# 10_eMMC.net
KiCad netlist of a schematic drawn in Altium Designer
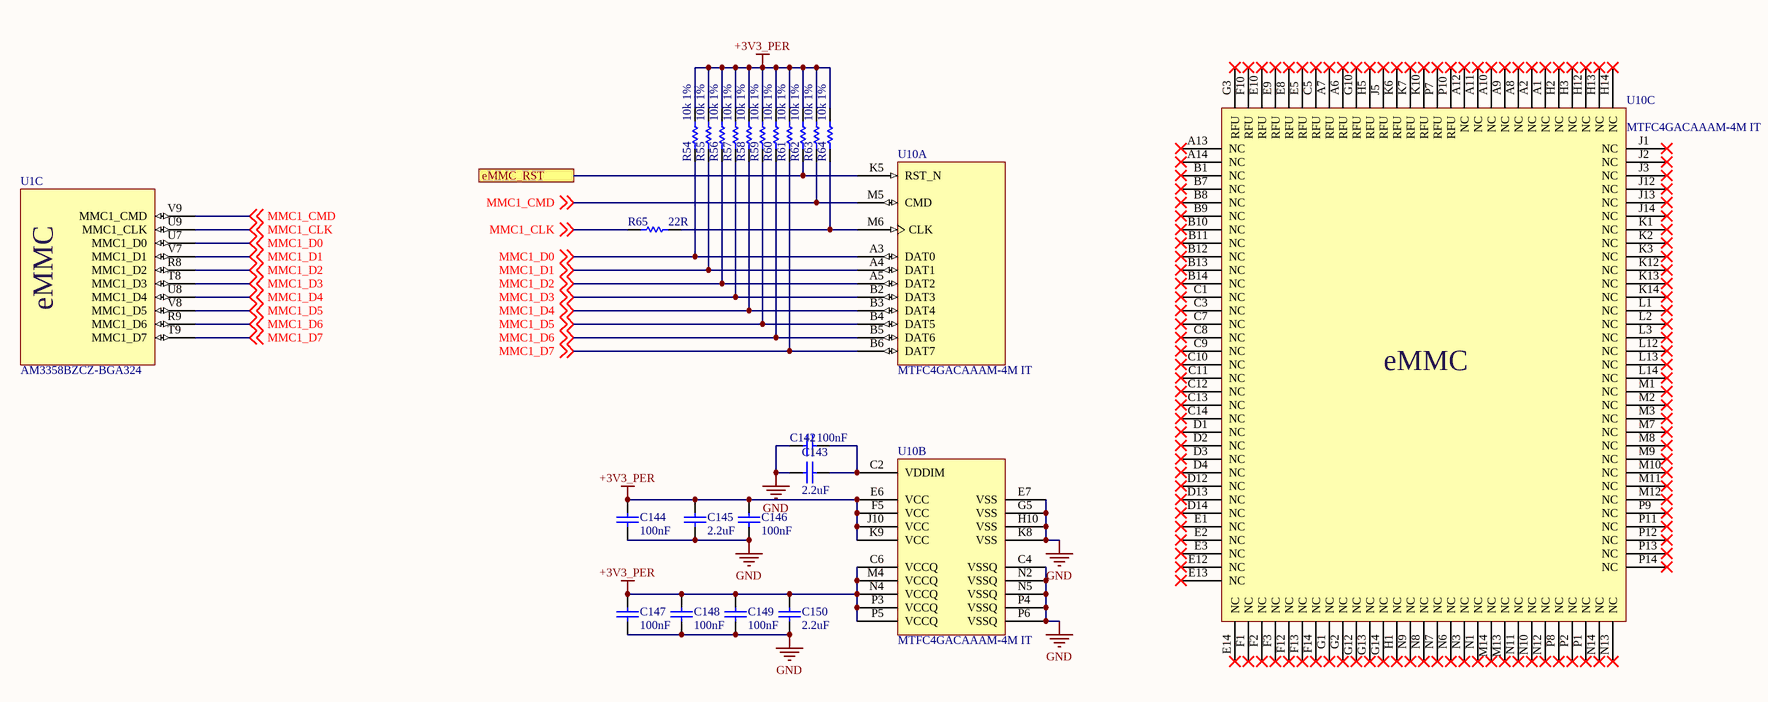
[diagram p0: 10. eMMC.SchDoc]

(export (version "E")
  (design (tool "Eeschema 10.0.6"))
  (components
    (comp (ref "C142")
      (value "100nF")
      (footprint "CAPC1005X60X30LL05T10")
      (description "Chip Capacitor, 0.1 uF, +/- 10%, 16 V, -55 to 125 degC, 0402 (1005 Metric), RoHS, Tape and Reel")
      (fields (field (name "VOLTAGE") "16V") (field (name "TOLERANCE") "10%"))
      (libsource (lib "AM3358_DEV_BOARD") (part "CAP-NP-2"))
    )
    (comp (ref "C143")
      (value "2.2uF")
      (footprint "CAPC1608X90X35ML10T15")
      (description "CAP 2.2uF 10V ±10% 0603 (1608 Metric) Thickness 0.6mm SMD")
      (fields (field (name "MANUFACTURER") "Murata") (field (name "PART NUMBER") "GRM188R71A225KE15D"))
      (libsource (lib "Altium Content Vault") (part "CAP"))
    )
    (comp (ref "C144")
      (value "100nF")
      (footprint "CAPC1005X60X30LL05T10")
      (description "Chip Capacitor, 0.1 uF, +/- 10%, 16 V, -55 to 125 degC, 0402 (1005 Metric), RoHS, Tape and Reel")
      (fields (field (name "VOLTAGE") "16V") (field (name "TOLERANCE") "10%"))
      (libsource (lib "AM3358_DEV_BOARD") (part "CAP-NP-2"))
    )
    (comp (ref "C145")
      (value "2.2uF")
      (footprint "CAPC1005X60X30LL05T10")
      (description "CAP 2.2uF 10V ±10% 0603 (1608 Metric) Thickness 0.6mm SMD")
      (fields (field (name "MANUFACTURER") "Murata") (field (name "PART NUMBER") "GRM188R71A225KE15D"))
      (libsource (lib "AM3358_DEV_BOARD") (part "CAP"))
    )
    (comp (ref "C146")
      (value "100nF")
      (footprint "CAPC1005X60X30LL05T10")
      (description "Chip Capacitor, 0.1 uF, +/- 10%, 16 V, -55 to 125 degC, 0402 (1005 Metric), RoHS, Tape and Reel")
      (fields (field (name "VOLTAGE") "16V") (field (name "TOLERANCE") "10%"))
      (libsource (lib "AM3358_DEV_BOARD") (part "CAP-NP-2"))
    )
    (comp (ref "C147")
      (value "100nF")
      (footprint "CAPC1005X60X30LL05T10")
      (description "Chip Capacitor, 0.1 uF, +/- 10%, 16 V, -55 to 125 degC, 0402 (1005 Metric), RoHS, Tape and Reel")
      (fields (field (name "VOLTAGE") "16V") (field (name "TOLERANCE") "10%"))
      (libsource (lib "AM3358_DEV_BOARD") (part "CAP-NP-2"))
    )
    (comp (ref "C148")
      (value "100nF")
      (footprint "CAPC1005X60X30LL05T10")
      (description "Chip Capacitor, 0.1 uF, +/- 10%, 16 V, -55 to 125 degC, 0402 (1005 Metric), RoHS, Tape and Reel")
      (fields (field (name "VOLTAGE") "16V") (field (name "TOLERANCE") "10%"))
      (libsource (lib "AM3358_DEV_BOARD") (part "CAP-NP-2"))
    )
    (comp (ref "C149")
      (value "100nF")
      (footprint "CAPC1005X60X30LL05T10")
      (description "Chip Capacitor, 0.1 uF, +/- 10%, 16 V, -55 to 125 degC, 0402 (1005 Metric), RoHS, Tape and Reel")
      (fields (field (name "VOLTAGE") "16V") (field (name "TOLERANCE") "10%"))
      (libsource (lib "AM3358_DEV_BOARD") (part "CAP-NP-2"))
    )
    (comp (ref "C150")
      (value "2.2uF")
      (footprint "CAPC1608X90X35ML10T15")
      (description "CAP 2.2uF 10V ±10% 0603 (1608 Metric) Thickness 0.6mm SMD")
      (fields (field (name "MANUFACTURER") "Murata") (field (name "PART NUMBER") "GRM188R71A225KE15D"))
      (libsource (lib "Altium Content Vault") (part "CAP"))
    )
    (comp (ref "R54")
      (value "10k 1%")
      (footprint "RESC1005X40X25LL05T05")
      (description "10k 0.063W 1% 0402 (1005 Metric)  SMD")
      (fields (field (name "MANUFACTURER") "Vishay Dale") (field (name "PART NUMBER") "CRCW040210K0FKED"))
      (libsource (lib "AM3358_DEV_BOARD") (part "RES"))
    )
    (comp (ref "R55")
      (value "10k 1%")
      (footprint "RESC1005X40X25LL05T05")
      (description "10k 0.063W 1% 0402 (1005 Metric)  SMD")
      (fields (field (name "MANUFACTURER") "Vishay Dale") (field (name "PART NUMBER") "CRCW040210K0FKED"))
      (libsource (lib "AM3358_DEV_BOARD") (part "RES"))
    )
    (comp (ref "R56")
      (value "10k 1%")
      (footprint "RESC1005X40X25LL05T05")
      (description "10k 0.063W 1% 0402 (1005 Metric)  SMD")
      (fields (field (name "MANUFACTURER") "Vishay Dale") (field (name "PART NUMBER") "CRCW040210K0FKED"))
      (libsource (lib "AM3358_DEV_BOARD") (part "RES"))
    )
    (comp (ref "R57")
      (value "10k 1%")
      (footprint "RESC1005X40X25LL05T05")
      (description "10k 0.063W 1% 0402 (1005 Metric)  SMD")
      (fields (field (name "MANUFACTURER") "Vishay Dale") (field (name "PART NUMBER") "CRCW040210K0FKED"))
      (libsource (lib "AM3358_DEV_BOARD") (part "RES"))
    )
    (comp (ref "R58")
      (value "10k 1%")
      (footprint "RESC1005X40X25LL05T05")
      (description "10k 0.063W 1% 0402 (1005 Metric)  SMD")
      (fields (field (name "MANUFACTURER") "Vishay Dale") (field (name "PART NUMBER") "CRCW040210K0FKED"))
      (libsource (lib "AM3358_DEV_BOARD") (part "RES"))
    )
    (comp (ref "R59")
      (value "10k 1%")
      (footprint "RESC1005X40X25LL05T05")
      (description "10k 0.063W 1% 0402 (1005 Metric)  SMD")
      (fields (field (name "MANUFACTURER") "Vishay Dale") (field (name "PART NUMBER") "CRCW040210K0FKED"))
      (libsource (lib "AM3358_DEV_BOARD") (part "RES"))
    )
    (comp (ref "R60")
      (value "10k 1%")
      (footprint "RESC1005X40X25LL05T05")
      (description "10k 0.063W 1% 0402 (1005 Metric)  SMD")
      (fields (field (name "MANUFACTURER") "Vishay Dale") (field (name "PART NUMBER") "CRCW040210K0FKED"))
      (libsource (lib "AM3358_DEV_BOARD") (part "RES"))
    )
    (comp (ref "R61")
      (value "10k 1%")
      (footprint "RESC1005X40X25LL05T05")
      (description "10k 0.063W 1% 0402 (1005 Metric)  SMD")
      (fields (field (name "MANUFACTURER") "Vishay Dale") (field (name "PART NUMBER") "CRCW040210K0FKED"))
      (libsource (lib "AM3358_DEV_BOARD") (part "RES"))
    )
    (comp (ref "R62")
      (value "10k 1%")
      (footprint "RESC1005X40X25LL05T05")
      (description "10k 0.063W 1% 0402 (1005 Metric)  SMD")
      (fields (field (name "MANUFACTURER") "Vishay Dale") (field (name "PART NUMBER") "CRCW040210K0FKED"))
      (libsource (lib "AM3358_DEV_BOARD") (part "RES"))
    )
    (comp (ref "R63")
      (value "10k 1%")
      (footprint "RESC1005X40X25LL05T05")
      (description "10k 0.063W 1% 0402 (1005 Metric)  SMD")
      (fields (field (name "MANUFACTURER") "Vishay Dale") (field (name "PART NUMBER") "CRCW040210K0FKED"))
      (libsource (lib "AM3358_DEV_BOARD") (part "RES"))
    )
    (comp (ref "R64")
      (value "10k 1%")
      (footprint "RESC1005X40X25LL05T05")
      (description "10k 0.063W 1% 0402 (1005 Metric)  SMD")
      (fields (field (name "MANUFACTURER") "Vishay Dale") (field (name "PART NUMBER") "CRCW040210K0FKED"))
      (libsource (lib "AM3358_DEV_BOARD") (part "RES"))
    )
    (comp (ref "R65")
      (value "22R")
      (footprint "RESC1005X40X25LL05T05")
      (description "Chip Resistor, 22 Ohm, +/- 1%, 0.1 W, -55 to 155 degC, 0402 (1005 Metric), RoHS, Tape and Reel")
      (fields (field (name "PARTNUMBER") "ERJ-2RKF22R0X") (field (name "TOLERANCE") "1%"))
      (libsource (lib "AM3358_DEV_BOARD") (part "RES-2"))
    )
    (comp (ref "U1")
      (value "AM3358BZCZ-BGA324")
      (footprint "TI-ZCZ324")
      (libsource (lib "SyTungNguyen") (part "AM3358BZCZ100"))
    )
    (comp (ref "U10")
      (value "MTFC4GACAAAM-4M IT")
      (footprint "VFBGA-153")
      (description "e·MMC Memory, 4 Gb, 2.7 to 3.6 V, -40 to 85 degC, 153-Ball VFBGA, RoHS")
      (fields (field (name "MANUFACTURER") "Micron"))
      (libsource (lib "AM3358_DEV_BOARD") (part "CMP-2000-05234-1"))
    )
  )
  (nets
    (net (code "1") (name "+3V3_PER") (class "Default")
      (node (ref "C144") (pin "2") (pinfunction "2_2") (pintype "passive"))
      (node (ref "C145") (pin "2") (pinfunction "2_2") (pintype "passive"))
      (node (ref "C146") (pin "2") (pinfunction "2_2") (pintype "passive"))
      (node (ref "C147") (pin "2") (pinfunction "2_2") (pintype "passive"))
      (node (ref "C148") (pin "2") (pinfunction "2_2") (pintype "passive"))
      (node (ref "C149") (pin "2") (pinfunction "2_2") (pintype "passive"))
      (node (ref "C150") (pin "2") (pinfunction "2_2") (pintype "passive"))
      (node (ref "R54") (pin "2") (pinfunction "2_2") (pintype "passive"))
      (node (ref "R55") (pin "2") (pinfunction "2_2") (pintype "passive"))
      (node (ref "R56") (pin "2") (pinfunction "2_2") (pintype "passive"))
      (node (ref "R57") (pin "2") (pinfunction "2_2") (pintype "passive"))
      (node (ref "R58") (pin "2") (pinfunction "2_2") (pintype "passive"))
      (node (ref "R59") (pin "2") (pinfunction "2_2") (pintype "passive"))
      (node (ref "R60") (pin "2") (pinfunction "2_2") (pintype "passive"))
      (node (ref "R61") (pin "2") (pinfunction "2_2") (pintype "passive"))
      (node (ref "R62") (pin "2") (pinfunction "2_2") (pintype "passive"))
      (node (ref "R63") (pin "2") (pinfunction "2_2") (pintype "passive"))
      (node (ref "R64") (pin "2") (pinfunction "2_2") (pintype "passive"))
      (node (ref "U10") (pin "C6") (pinfunction "VCCQ_C6") (pintype "power_in"))
      (node (ref "U10") (pin "E6") (pinfunction "VCC_E6") (pintype "power_in"))
      (node (ref "U10") (pin "F5") (pinfunction "VCC_F5") (pintype "power_in"))
      (node (ref "U10") (pin "J10") (pinfunction "VCC_J10") (pintype "power_in"))
      (node (ref "U10") (pin "K9") (pinfunction "VCC_K9") (pintype "power_in"))
      (node (ref "U10") (pin "M4") (pinfunction "VCCQ_M4") (pintype "power_in"))
      (node (ref "U10") (pin "N4") (pinfunction "VCCQ_N4") (pintype "power_in"))
      (node (ref "U10") (pin "P3") (pinfunction "VCCQ_P3") (pintype "power_in"))
      (node (ref "U10") (pin "P5") (pinfunction "VCCQ_P5") (pintype "power_in"))
    )
    (net (code "2") (name "/eMMC_RST") (class "Default")
      (node (ref "R62") (pin "1") (pinfunction "1_1") (pintype "passive"))
      (node (ref "U10") (pin "K5") (pinfunction "RST_N_K5") (pintype "input"))
    )
    (net (code "3") (name "GND") (class "Default")
      (node (ref "C142") (pin "2") (pinfunction "2_2") (pintype "passive"))
      (node (ref "C143") (pin "2") (pinfunction "2_2") (pintype "passive"))
      (node (ref "C144") (pin "1") (pinfunction "1_1") (pintype "passive"))
      (node (ref "C145") (pin "1") (pinfunction "1_1") (pintype "passive"))
      (node (ref "C146") (pin "1") (pinfunction "1_1") (pintype "passive"))
      (node (ref "C147") (pin "1") (pinfunction "1_1") (pintype "passive"))
      (node (ref "C148") (pin "1") (pinfunction "1_1") (pintype "passive"))
      (node (ref "C149") (pin "1") (pinfunction "1_1") (pintype "passive"))
      (node (ref "C150") (pin "1") (pinfunction "1_1") (pintype "passive"))
      (node (ref "U10") (pin "C4") (pinfunction "VSSQ_C4") (pintype "power_in"))
      (node (ref "U10") (pin "E7") (pinfunction "VSS_E7") (pintype "power_in"))
      (node (ref "U10") (pin "G5") (pinfunction "VSS_G5") (pintype "power_in"))
      (node (ref "U10") (pin "H10") (pinfunction "VSS_H10") (pintype "power_in"))
      (node (ref "U10") (pin "K8") (pinfunction "VSS_K8") (pintype "power_in"))
      (node (ref "U10") (pin "N2") (pinfunction "VSSQ_N2") (pintype "power_in"))
      (node (ref "U10") (pin "N5") (pinfunction "VSSQ_N5") (pintype "power_in"))
      (node (ref "U10") (pin "P4") (pinfunction "VSSQ_P4") (pintype "power_in"))
      (node (ref "U10") (pin "P6") (pinfunction "VSSQ_P6") (pintype "power_in"))
    )
    (net (code "4") (name "MMC1_CLK") (class "Default")
      (node (ref "R65") (pin "1") (pinfunction "1_1") (pintype "passive"))
      (node (ref "U1") (pin "U9") (pinfunction "MMC1_CLK_U9") (pintype "bidirectional"))
    )
    (net (code "5") (name "MMC1_CMD") (class "Default")
      (node (ref "R63") (pin "1") (pinfunction "1_1") (pintype "passive"))
      (node (ref "U1") (pin "V9") (pinfunction "MMC1_CMD_V9") (pintype "bidirectional"))
      (node (ref "U10") (pin "M5") (pinfunction "CMD_M5") (pintype "bidirectional"))
    )
    (net (code "6") (name "MMC1_D0") (class "Default")
      (node (ref "R54") (pin "1") (pinfunction "1_1") (pintype "passive"))
      (node (ref "U1") (pin "U7") (pinfunction "MMC1_D0_U7") (pintype "bidirectional"))
      (node (ref "U10") (pin "A3") (pinfunction "DAT0_A3") (pintype "bidirectional"))
    )
    (net (code "7") (name "MMC1_D1") (class "Default")
      (node (ref "R55") (pin "1") (pinfunction "1_1") (pintype "passive"))
      (node (ref "U1") (pin "V7") (pinfunction "MMC1_D1_V7") (pintype "bidirectional"))
      (node (ref "U10") (pin "A4") (pinfunction "DAT1_A4") (pintype "bidirectional"))
    )
    (net (code "8") (name "MMC1_D2") (class "Default")
      (node (ref "R56") (pin "1") (pinfunction "1_1") (pintype "passive"))
      (node (ref "U1") (pin "R8") (pinfunction "MMC1_D2_R8") (pintype "bidirectional"))
      (node (ref "U10") (pin "A5") (pinfunction "DAT2_A5") (pintype "bidirectional"))
    )
    (net (code "9") (name "MMC1_D3") (class "Default")
      (node (ref "R57") (pin "1") (pinfunction "1_1") (pintype "passive"))
      (node (ref "U1") (pin "T8") (pinfunction "MMC1_D3_T8") (pintype "bidirectional"))
      (node (ref "U10") (pin "B2") (pinfunction "DAT3_B2") (pintype "bidirectional"))
    )
    (net (code "10") (name "MMC1_D4") (class "Default")
      (node (ref "R58") (pin "1") (pinfunction "1_1") (pintype "passive"))
      (node (ref "U1") (pin "U8") (pinfunction "MMC1_D4_U8") (pintype "bidirectional"))
      (node (ref "U10") (pin "B3") (pinfunction "DAT4_B3") (pintype "bidirectional"))
    )
    (net (code "11") (name "MMC1_D5") (class "Default")
      (node (ref "R59") (pin "1") (pinfunction "1_1") (pintype "passive"))
      (node (ref "U1") (pin "V8") (pinfunction "MMC1_D5_V8") (pintype "bidirectional"))
      (node (ref "U10") (pin "B4") (pinfunction "DAT5_B4") (pintype "bidirectional"))
    )
    (net (code "12") (name "MMC1_D6") (class "Default")
      (node (ref "R60") (pin "1") (pinfunction "1_1") (pintype "passive"))
      (node (ref "U1") (pin "R9") (pinfunction "MMC1_D6_R9") (pintype "bidirectional"))
      (node (ref "U10") (pin "B5") (pinfunction "DAT6_B5") (pintype "bidirectional"))
    )
    (net (code "13") (name "MMC1_D7") (class "Default")
      (node (ref "R61") (pin "1") (pinfunction "1_1") (pintype "passive"))
      (node (ref "U1") (pin "T9") (pinfunction "MMC1_D7_T9") (pintype "bidirectional"))
      (node (ref "U10") (pin "B6") (pinfunction "DAT7_B6") (pintype "bidirectional"))
    )
    (net (code "14") (name "Net-(U10A-CLK)") (class "Default")
      (node (ref "R64") (pin "1") (pinfunction "1_1") (pintype "passive"))
      (node (ref "R65") (pin "2") (pinfunction "2_2") (pintype "passive"))
      (node (ref "U10") (pin "M6") (pinfunction "CLK_M6") (pintype "input"))
    )
    (net (code "15") (name "Net-(U10B-VDDIM)") (class "Default")
      (node (ref "C142") (pin "1") (pinfunction "1_1") (pintype "passive"))
      (node (ref "C143") (pin "1") (pinfunction "1_1") (pintype "passive"))
      (node (ref "U10") (pin "C2") (pinfunction "VDDIM_C2") (pintype "power_in"))
    )
    (net (code "16") (name "unconnected-(U10C-NC-PadA1)") (class "Default")
      (node (ref "U10") (pin "A1") (pinfunction "NC_A1") (pintype "passive+no_connect"))
    )
    (net (code "17") (name "unconnected-(U10C-NC-PadA2)") (class "Default")
      (node (ref "U10") (pin "A2") (pinfunction "NC_A2") (pintype "passive+no_connect"))
    )
    (net (code "18") (name "unconnected-(U10C-NC-PadA8)") (class "Default")
      (node (ref "U10") (pin "A8") (pinfunction "NC_A8") (pintype "passive+no_connect"))
    )
    (net (code "19") (name "unconnected-(U10C-NC-PadA9)") (class "Default")
      (node (ref "U10") (pin "A9") (pinfunction "NC_A9") (pintype "passive+no_connect"))
    )
    (net (code "20") (name "unconnected-(U10C-NC-PadA10)") (class "Default")
      (node (ref "U10") (pin "A10") (pinfunction "NC_A10") (pintype "passive+no_connect"))
    )
    (net (code "21") (name "unconnected-(U10C-NC-PadA11)") (class "Default")
      (node (ref "U10") (pin "A11") (pinfunction "NC_A11") (pintype "passive+no_connect"))
    )
    (net (code "22") (name "unconnected-(U10C-NC-PadA12)") (class "Default")
      (node (ref "U10") (pin "A12") (pinfunction "NC_A12") (pintype "passive+no_connect"))
    )
    (net (code "23") (name "unconnected-(U10C-NC-PadA13)") (class "Default")
      (node (ref "U10") (pin "A13") (pinfunction "NC_A13") (pintype "passive+no_connect"))
    )
    (net (code "24") (name "unconnected-(U10C-NC-PadA14)") (class "Default")
      (node (ref "U10") (pin "A14") (pinfunction "NC_A14") (pintype "passive+no_connect"))
    )
    (net (code "25") (name "unconnected-(U10C-NC-PadB1)") (class "Default")
      (node (ref "U10") (pin "B1") (pinfunction "NC_B1") (pintype "passive+no_connect"))
    )
    (net (code "26") (name "unconnected-(U10C-NC-PadB7)") (class "Default")
      (node (ref "U10") (pin "B7") (pinfunction "NC_B7") (pintype "passive+no_connect"))
    )
    (net (code "27") (name "unconnected-(U10C-NC-PadB8)") (class "Default")
      (node (ref "U10") (pin "B8") (pinfunction "NC_B8") (pintype "passive+no_connect"))
    )
    (net (code "28") (name "unconnected-(U10C-NC-PadB9)") (class "Default")
      (node (ref "U10") (pin "B9") (pinfunction "NC_B9") (pintype "passive+no_connect"))
    )
    (net (code "29") (name "unconnected-(U10C-NC-PadB10)") (class "Default")
      (node (ref "U10") (pin "B10") (pinfunction "NC_B10") (pintype "passive+no_connect"))
    )
    (net (code "30") (name "unconnected-(U10C-NC-PadB11)") (class "Default")
      (node (ref "U10") (pin "B11") (pinfunction "NC_B11") (pintype "passive+no_connect"))
    )
    (net (code "31") (name "unconnected-(U10C-NC-PadB12)") (class "Default")
      (node (ref "U10") (pin "B12") (pinfunction "NC_B12") (pintype "passive+no_connect"))
    )
    (net (code "32") (name "unconnected-(U10C-NC-PadB13)") (class "Default")
      (node (ref "U10") (pin "B13") (pinfunction "NC_B13") (pintype "passive+no_connect"))
    )
    (net (code "33") (name "unconnected-(U10C-NC-PadB14)") (class "Default")
      (node (ref "U10") (pin "B14") (pinfunction "NC_B14") (pintype "passive+no_connect"))
    )
    (net (code "34") (name "unconnected-(U10C-NC-PadC1)") (class "Default")
      (node (ref "U10") (pin "C1") (pinfunction "NC_C1") (pintype "passive+no_connect"))
    )
    (net (code "35") (name "unconnected-(U10C-NC-PadC3)") (class "Default")
      (node (ref "U10") (pin "C3") (pinfunction "NC_C3") (pintype "passive+no_connect"))
    )
    (net (code "36") (name "unconnected-(U10C-NC-PadC7)") (class "Default")
      (node (ref "U10") (pin "C7") (pinfunction "NC_C7") (pintype "passive+no_connect"))
    )
    (net (code "37") (name "unconnected-(U10C-NC-PadC8)") (class "Default")
      (node (ref "U10") (pin "C8") (pinfunction "NC_C8") (pintype "passive+no_connect"))
    )
    (net (code "38") (name "unconnected-(U10C-NC-PadC9)") (class "Default")
      (node (ref "U10") (pin "C9") (pinfunction "NC_C9") (pintype "passive+no_connect"))
    )
    (net (code "39") (name "unconnected-(U10C-NC-PadC10)") (class "Default")
      (node (ref "U10") (pin "C10") (pinfunction "NC_C10") (pintype "passive+no_connect"))
    )
    (net (code "40") (name "unconnected-(U10C-NC-PadC11)") (class "Default")
      (node (ref "U10") (pin "C11") (pinfunction "NC_C11") (pintype "passive+no_connect"))
    )
    (net (code "41") (name "unconnected-(U10C-NC-PadC12)") (class "Default")
      (node (ref "U10") (pin "C12") (pinfunction "NC_C12") (pintype "passive+no_connect"))
    )
    (net (code "42") (name "unconnected-(U10C-NC-PadC13)") (class "Default")
      (node (ref "U10") (pin "C13") (pinfunction "NC_C13") (pintype "passive+no_connect"))
    )
    (net (code "43") (name "unconnected-(U10C-NC-PadC14)") (class "Default")
      (node (ref "U10") (pin "C14") (pinfunction "NC_C14") (pintype "passive+no_connect"))
    )
    (net (code "44") (name "unconnected-(U10C-NC-PadD1)") (class "Default")
      (node (ref "U10") (pin "D1") (pinfunction "NC_D1") (pintype "passive+no_connect"))
    )
    (net (code "45") (name "unconnected-(U10C-NC-PadD2)") (class "Default")
      (node (ref "U10") (pin "D2") (pinfunction "NC_D2") (pintype "passive+no_connect"))
    )
    (net (code "46") (name "unconnected-(U10C-NC-PadD3)") (class "Default")
      (node (ref "U10") (pin "D3") (pinfunction "NC_D3") (pintype "passive+no_connect"))
    )
    (net (code "47") (name "unconnected-(U10C-NC-PadD4)") (class "Default")
      (node (ref "U10") (pin "D4") (pinfunction "NC_D4") (pintype "passive+no_connect"))
    )
    (net (code "48") (name "unconnected-(U10C-NC-PadD12)") (class "Default")
      (node (ref "U10") (pin "D12") (pinfunction "NC_D12") (pintype "passive+no_connect"))
    )
    (net (code "49") (name "unconnected-(U10C-NC-PadD13)") (class "Default")
      (node (ref "U10") (pin "D13") (pinfunction "NC_D13") (pintype "passive+no_connect"))
    )
    (net (code "50") (name "unconnected-(U10C-NC-PadD14)") (class "Default")
      (node (ref "U10") (pin "D14") (pinfunction "NC_D14") (pintype "passive+no_connect"))
    )
    (net (code "51") (name "unconnected-(U10C-NC-PadE1)") (class "Default")
      (node (ref "U10") (pin "E1") (pinfunction "NC_E1") (pintype "passive+no_connect"))
    )
    (net (code "52") (name "unconnected-(U10C-NC-PadE2)") (class "Default")
      (node (ref "U10") (pin "E2") (pinfunction "NC_E2") (pintype "passive+no_connect"))
    )
    (net (code "53") (name "unconnected-(U10C-NC-PadE3)") (class "Default")
      (node (ref "U10") (pin "E3") (pinfunction "NC_E3") (pintype "passive+no_connect"))
    )
    (net (code "54") (name "unconnected-(U10C-NC-PadE12)") (class "Default")
      (node (ref "U10") (pin "E12") (pinfunction "NC_E12") (pintype "passive+no_connect"))
    )
    (net (code "55") (name "unconnected-(U10C-NC-PadE13)") (class "Default")
      (node (ref "U10") (pin "E13") (pinfunction "NC_E13") (pintype "passive+no_connect"))
    )
    (net (code "56") (name "unconnected-(U10C-NC-PadE14)") (class "Default")
      (node (ref "U10") (pin "E14") (pinfunction "NC_E14") (pintype "passive+no_connect"))
    )
    (net (code "57") (name "unconnected-(U10C-NC-PadF1)") (class "Default")
      (node (ref "U10") (pin "F1") (pinfunction "NC_F1") (pintype "passive+no_connect"))
    )
    (net (code "58") (name "unconnected-(U10C-NC-PadF2)") (class "Default")
      (node (ref "U10") (pin "F2") (pinfunction "NC_F2") (pintype "passive+no_connect"))
    )
    (net (code "59") (name "unconnected-(U10C-NC-PadF3)") (class "Default")
      (node (ref "U10") (pin "F3") (pinfunction "NC_F3") (pintype "passive+no_connect"))
    )
    (net (code "60") (name "unconnected-(U10C-NC-PadF12)") (class "Default")
      (node (ref "U10") (pin "F12") (pinfunction "NC_F12") (pintype "passive+no_connect"))
    )
    (net (code "61") (name "unconnected-(U10C-NC-PadF13)") (class "Default")
      (node (ref "U10") (pin "F13") (pinfunction "NC_F13") (pintype "passive+no_connect"))
    )
    (net (code "62") (name "unconnected-(U10C-NC-PadF14)") (class "Default")
      (node (ref "U10") (pin "F14") (pinfunction "NC_F14") (pintype "passive+no_connect"))
    )
    (net (code "63") (name "unconnected-(U10C-NC-PadG1)") (class "Default")
      (node (ref "U10") (pin "G1") (pinfunction "NC_G1") (pintype "passive+no_connect"))
    )
    (net (code "64") (name "unconnected-(U10C-NC-PadG2)") (class "Default")
      (node (ref "U10") (pin "G2") (pinfunction "NC_G2") (pintype "passive+no_connect"))
    )
    (net (code "65") (name "unconnected-(U10C-NC-PadG12)") (class "Default")
      (node (ref "U10") (pin "G12") (pinfunction "NC_G12") (pintype "passive+no_connect"))
    )
    (net (code "66") (name "unconnected-(U10C-NC-PadG13)") (class "Default")
      (node (ref "U10") (pin "G13") (pinfunction "NC_G13") (pintype "passive+no_connect"))
    )
    (net (code "67") (name "unconnected-(U10C-NC-PadG14)") (class "Default")
      (node (ref "U10") (pin "G14") (pinfunction "NC_G14") (pintype "passive+no_connect"))
    )
    (net (code "68") (name "unconnected-(U10C-NC-PadH1)") (class "Default")
      (node (ref "U10") (pin "H1") (pinfunction "NC_H1") (pintype "passive+no_connect"))
    )
    (net (code "69") (name "unconnected-(U10C-NC-PadH2)") (class "Default")
      (node (ref "U10") (pin "H2") (pinfunction "NC_H2") (pintype "passive+no_connect"))
    )
    (net (code "70") (name "unconnected-(U10C-NC-PadH3)") (class "Default")
      (node (ref "U10") (pin "H3") (pinfunction "NC_H3") (pintype "passive+no_connect"))
    )
    (net (code "71") (name "unconnected-(U10C-NC-PadH12)") (class "Default")
      (node (ref "U10") (pin "H12") (pinfunction "NC_H12") (pintype "passive+no_connect"))
    )
    (net (code "72") (name "unconnected-(U10C-NC-PadH13)") (class "Default")
      (node (ref "U10") (pin "H13") (pinfunction "NC_H13") (pintype "passive+no_connect"))
    )
    (net (code "73") (name "unconnected-(U10C-NC-PadH14)") (class "Default")
      (node (ref "U10") (pin "H14") (pinfunction "NC_H14") (pintype "passive+no_connect"))
    )
    (net (code "74") (name "unconnected-(U10C-NC-PadJ1)") (class "Default")
      (node (ref "U10") (pin "J1") (pinfunction "NC_J1") (pintype "passive+no_connect"))
    )
    (net (code "75") (name "unconnected-(U10C-NC-PadJ2)") (class "Default")
      (node (ref "U10") (pin "J2") (pinfunction "NC_J2") (pintype "passive+no_connect"))
    )
    (net (code "76") (name "unconnected-(U10C-NC-PadJ3)") (class "Default")
      (node (ref "U10") (pin "J3") (pinfunction "NC_J3") (pintype "passive+no_connect"))
    )
    (net (code "77") (name "unconnected-(U10C-NC-PadJ12)") (class "Default")
      (node (ref "U10") (pin "J12") (pinfunction "NC_J12") (pintype "passive+no_connect"))
    )
    (net (code "78") (name "unconnected-(U10C-NC-PadJ13)") (class "Default")
      (node (ref "U10") (pin "J13") (pinfunction "NC_J13") (pintype "passive+no_connect"))
    )
    (net (code "79") (name "unconnected-(U10C-NC-PadJ14)") (class "Default")
      (node (ref "U10") (pin "J14") (pinfunction "NC_J14") (pintype "passive+no_connect"))
    )
    (net (code "80") (name "unconnected-(U10C-NC-PadK1)") (class "Default")
      (node (ref "U10") (pin "K1") (pinfunction "NC_K1") (pintype "passive+no_connect"))
    )
    (net (code "81") (name "unconnected-(U10C-NC-PadK2)") (class "Default")
      (node (ref "U10") (pin "K2") (pinfunction "NC_K2") (pintype "passive+no_connect"))
    )
    (net (code "82") (name "unconnected-(U10C-NC-PadK3)") (class "Default")
      (node (ref "U10") (pin "K3") (pinfunction "NC_K3") (pintype "passive+no_connect"))
    )
    (net (code "83") (name "unconnected-(U10C-NC-PadK12)") (class "Default")
      (node (ref "U10") (pin "K12") (pinfunction "NC_K12") (pintype "passive+no_connect"))
    )
    (net (code "84") (name "unconnected-(U10C-NC-PadK13)") (class "Default")
      (node (ref "U10") (pin "K13") (pinfunction "NC_K13") (pintype "passive+no_connect"))
    )
    (net (code "85") (name "unconnected-(U10C-NC-PadK14)") (class "Default")
      (node (ref "U10") (pin "K14") (pinfunction "NC_K14") (pintype "passive+no_connect"))
    )
    (net (code "86") (name "unconnected-(U10C-NC-PadL1)") (class "Default")
      (node (ref "U10") (pin "L1") (pinfunction "NC_L1") (pintype "passive+no_connect"))
    )
    (net (code "87") (name "unconnected-(U10C-NC-PadL2)") (class "Default")
      (node (ref "U10") (pin "L2") (pinfunction "NC_L2") (pintype "passive+no_connect"))
    )
    (net (code "88") (name "unconnected-(U10C-NC-PadL3)") (class "Default")
      (node (ref "U10") (pin "L3") (pinfunction "NC_L3") (pintype "passive+no_connect"))
    )
    (net (code "89") (name "unconnected-(U10C-NC-PadL12)") (class "Default")
      (node (ref "U10") (pin "L12") (pinfunction "NC_L12") (pintype "passive+no_connect"))
    )
    (net (code "90") (name "unconnected-(U10C-NC-PadL13)") (class "Default")
      (node (ref "U10") (pin "L13") (pinfunction "NC_L13") (pintype "passive+no_connect"))
    )
    (net (code "91") (name "unconnected-(U10C-NC-PadL14)") (class "Default")
      (node (ref "U10") (pin "L14") (pinfunction "NC_L14") (pintype "passive+no_connect"))
    )
    (net (code "92") (name "unconnected-(U10C-NC-PadM1)") (class "Default")
      (node (ref "U10") (pin "M1") (pinfunction "NC_M1") (pintype "passive+no_connect"))
    )
    (net (code "93") (name "unconnected-(U10C-NC-PadM2)") (class "Default")
      (node (ref "U10") (pin "M2") (pinfunction "NC_M2") (pintype "passive+no_connect"))
    )
    (net (code "94") (name "unconnected-(U10C-NC-PadM3)") (class "Default")
      (node (ref "U10") (pin "M3") (pinfunction "NC_M3") (pintype "passive+no_connect"))
    )
    (net (code "95") (name "unconnected-(U10C-NC-PadM7)") (class "Default")
      (node (ref "U10") (pin "M7") (pinfunction "NC_M7") (pintype "passive+no_connect"))
    )
    (net (code "96") (name "unconnected-(U10C-NC-PadM8)") (class "Default")
      (node (ref "U10") (pin "M8") (pinfunction "NC_M8") (pintype "passive+no_connect"))
    )
    (net (code "97") (name "unconnected-(U10C-NC-PadM9)") (class "Default")
      (node (ref "U10") (pin "M9") (pinfunction "NC_M9") (pintype "passive+no_connect"))
    )
    (net (code "98") (name "unconnected-(U10C-NC-PadM10)") (class "Default")
      (node (ref "U10") (pin "M10") (pinfunction "NC_M10") (pintype "passive+no_connect"))
    )
    (net (code "99") (name "unconnected-(U10C-NC-PadM11)") (class "Default")
      (node (ref "U10") (pin "M11") (pinfunction "NC_M11") (pintype "passive+no_connect"))
    )
    (net (code "100") (name "unconnected-(U10C-NC-PadM12)") (class "Default")
      (node (ref "U10") (pin "M12") (pinfunction "NC_M12") (pintype "passive+no_connect"))
    )
    (net (code "101") (name "unconnected-(U10C-NC-PadM13)") (class "Default")
      (node (ref "U10") (pin "M13") (pinfunction "NC_M13") (pintype "passive+no_connect"))
    )
    (net (code "102") (name "unconnected-(U10C-NC-PadM14)") (class "Default")
      (node (ref "U10") (pin "M14") (pinfunction "NC_M14") (pintype "passive+no_connect"))
    )
    (net (code "103") (name "unconnected-(U10C-NC-PadN1)") (class "Default")
      (node (ref "U10") (pin "N1") (pinfunction "NC_N1") (pintype "passive+no_connect"))
    )
    (net (code "104") (name "unconnected-(U10C-NC-PadN3)") (class "Default")
      (node (ref "U10") (pin "N3") (pinfunction "NC_N3") (pintype "passive+no_connect"))
    )
    (net (code "105") (name "unconnected-(U10C-NC-PadN6)") (class "Default")
      (node (ref "U10") (pin "N6") (pinfunction "NC_N6") (pintype "passive+no_connect"))
    )
    (net (code "106") (name "unconnected-(U10C-NC-PadN7)") (class "Default")
      (node (ref "U10") (pin "N7") (pinfunction "NC_N7") (pintype "passive+no_connect"))
    )
    (net (code "107") (name "unconnected-(U10C-NC-PadN8)") (class "Default")
      (node (ref "U10") (pin "N8") (pinfunction "NC_N8") (pintype "passive+no_connect"))
    )
    (net (code "108") (name "unconnected-(U10C-NC-PadN9)") (class "Default")
      (node (ref "U10") (pin "N9") (pinfunction "NC_N9") (pintype "passive+no_connect"))
    )
    (net (code "109") (name "unconnected-(U10C-NC-PadN10)") (class "Default")
      (node (ref "U10") (pin "N10") (pinfunction "NC_N10") (pintype "passive+no_connect"))
    )
    (net (code "110") (name "unconnected-(U10C-NC-PadN11)") (class "Default")
      (node (ref "U10") (pin "N11") (pinfunction "NC_N11") (pintype "passive+no_connect"))
    )
    (net (code "111") (name "unconnected-(U10C-NC-PadN12)") (class "Default")
      (node (ref "U10") (pin "N12") (pinfunction "NC_N12") (pintype "passive+no_connect"))
    )
    (net (code "112") (name "unconnected-(U10C-NC-PadN13)") (class "Default")
      (node (ref "U10") (pin "N13") (pinfunction "NC_N13") (pintype "passive+no_connect"))
    )
    (net (code "113") (name "unconnected-(U10C-NC-PadN14)") (class "Default")
      (node (ref "U10") (pin "N14") (pinfunction "NC_N14") (pintype "passive+no_connect"))
    )
    (net (code "114") (name "unconnected-(U10C-NC-PadP1)") (class "Default")
      (node (ref "U10") (pin "P1") (pinfunction "NC_P1") (pintype "passive+no_connect"))
    )
    (net (code "115") (name "unconnected-(U10C-NC-PadP2)") (class "Default")
      (node (ref "U10") (pin "P2") (pinfunction "NC_P2") (pintype "passive+no_connect"))
    )
    (net (code "116") (name "unconnected-(U10C-NC-PadP8)") (class "Default")
      (node (ref "U10") (pin "P8") (pinfunction "NC_P8") (pintype "passive+no_connect"))
    )
    (net (code "117") (name "unconnected-(U10C-NC-PadP9)") (class "Default")
      (node (ref "U10") (pin "P9") (pinfunction "NC_P9") (pintype "passive+no_connect"))
    )
    (net (code "118") (name "unconnected-(U10C-NC-PadP11)") (class "Default")
      (node (ref "U10") (pin "P11") (pinfunction "NC_P11") (pintype "passive+no_connect"))
    )
    (net (code "119") (name "unconnected-(U10C-NC-PadP12)") (class "Default")
      (node (ref "U10") (pin "P12") (pinfunction "NC_P12") (pintype "passive+no_connect"))
    )
    (net (code "120") (name "unconnected-(U10C-NC-PadP13)") (class "Default")
      (node (ref "U10") (pin "P13") (pinfunction "NC_P13") (pintype "passive+no_connect"))
    )
    (net (code "121") (name "unconnected-(U10C-NC-PadP14)") (class "Default")
      (node (ref "U10") (pin "P14") (pinfunction "NC_P14") (pintype "passive+no_connect"))
    )
    (net (code "122") (name "unconnected-(U10C-RFU-PadA6)") (class "Default")
      (node (ref "U10") (pin "A6") (pinfunction "RFU_A6") (pintype "passive+no_connect"))
    )
    (net (code "123") (name "unconnected-(U10C-RFU-PadA7)") (class "Default")
      (node (ref "U10") (pin "A7") (pinfunction "RFU_A7") (pintype "passive+no_connect"))
    )
    (net (code "124") (name "unconnected-(U10C-RFU-PadC5)") (class "Default")
      (node (ref "U10") (pin "C5") (pinfunction "RFU_C5") (pintype "passive+no_connect"))
    )
    (net (code "125") (name "unconnected-(U10C-RFU-PadE5)") (class "Default")
      (node (ref "U10") (pin "E5") (pinfunction "RFU_E5") (pintype "passive+no_connect"))
    )
    (net (code "126") (name "unconnected-(U10C-RFU-PadE8)") (class "Default")
      (node (ref "U10") (pin "E8") (pinfunction "RFU_E8") (pintype "passive+no_connect"))
    )
    (net (code "127") (name "unconnected-(U10C-RFU-PadE9)") (class "Default")
      (node (ref "U10") (pin "E9") (pinfunction "RFU_E9") (pintype "passive+no_connect"))
    )
    (net (code "128") (name "unconnected-(U10C-RFU-PadE10)") (class "Default")
      (node (ref "U10") (pin "E10") (pinfunction "RFU_E10") (pintype "passive+no_connect"))
    )
    (net (code "129") (name "unconnected-(U10C-RFU-PadF10)") (class "Default")
      (node (ref "U10") (pin "F10") (pinfunction "RFU_F10") (pintype "passive+no_connect"))
    )
    (net (code "130") (name "unconnected-(U10C-RFU-PadG3)") (class "Default")
      (node (ref "U10") (pin "G3") (pinfunction "RFU_G3") (pintype "passive+no_connect"))
    )
    (net (code "131") (name "unconnected-(U10C-RFU-PadG10)") (class "Default")
      (node (ref "U10") (pin "G10") (pinfunction "RFU_G10") (pintype "passive+no_connect"))
    )
    (net (code "132") (name "unconnected-(U10C-RFU-PadH5)") (class "Default")
      (node (ref "U10") (pin "H5") (pinfunction "RFU_H5") (pintype "passive+no_connect"))
    )
    (net (code "133") (name "unconnected-(U10C-RFU-PadJ5)") (class "Default")
      (node (ref "U10") (pin "J5") (pinfunction "RFU_J5") (pintype "passive+no_connect"))
    )
    (net (code "134") (name "unconnected-(U10C-RFU-PadK6)") (class "Default")
      (node (ref "U10") (pin "K6") (pinfunction "RFU_K6") (pintype "passive+no_connect"))
    )
    (net (code "135") (name "unconnected-(U10C-RFU-PadK7)") (class "Default")
      (node (ref "U10") (pin "K7") (pinfunction "RFU_K7") (pintype "passive+no_connect"))
    )
    (net (code "136") (name "unconnected-(U10C-RFU-PadK10)") (class "Default")
      (node (ref "U10") (pin "K10") (pinfunction "RFU_K10") (pintype "passive+no_connect"))
    )
    (net (code "137") (name "unconnected-(U10C-RFU-PadP7)") (class "Default")
      (node (ref "U10") (pin "P7") (pinfunction "RFU_P7") (pintype "passive+no_connect"))
    )
    (net (code "138") (name "unconnected-(U10C-RFU-PadP10)") (class "Default")
      (node (ref "U10") (pin "P10") (pinfunction "RFU_P10") (pintype "passive+no_connect"))
    )
  )
)
